# temp-stellwerk-a-3-laser-2.net
KiCad netlist of a schematic drawn in EAGLE
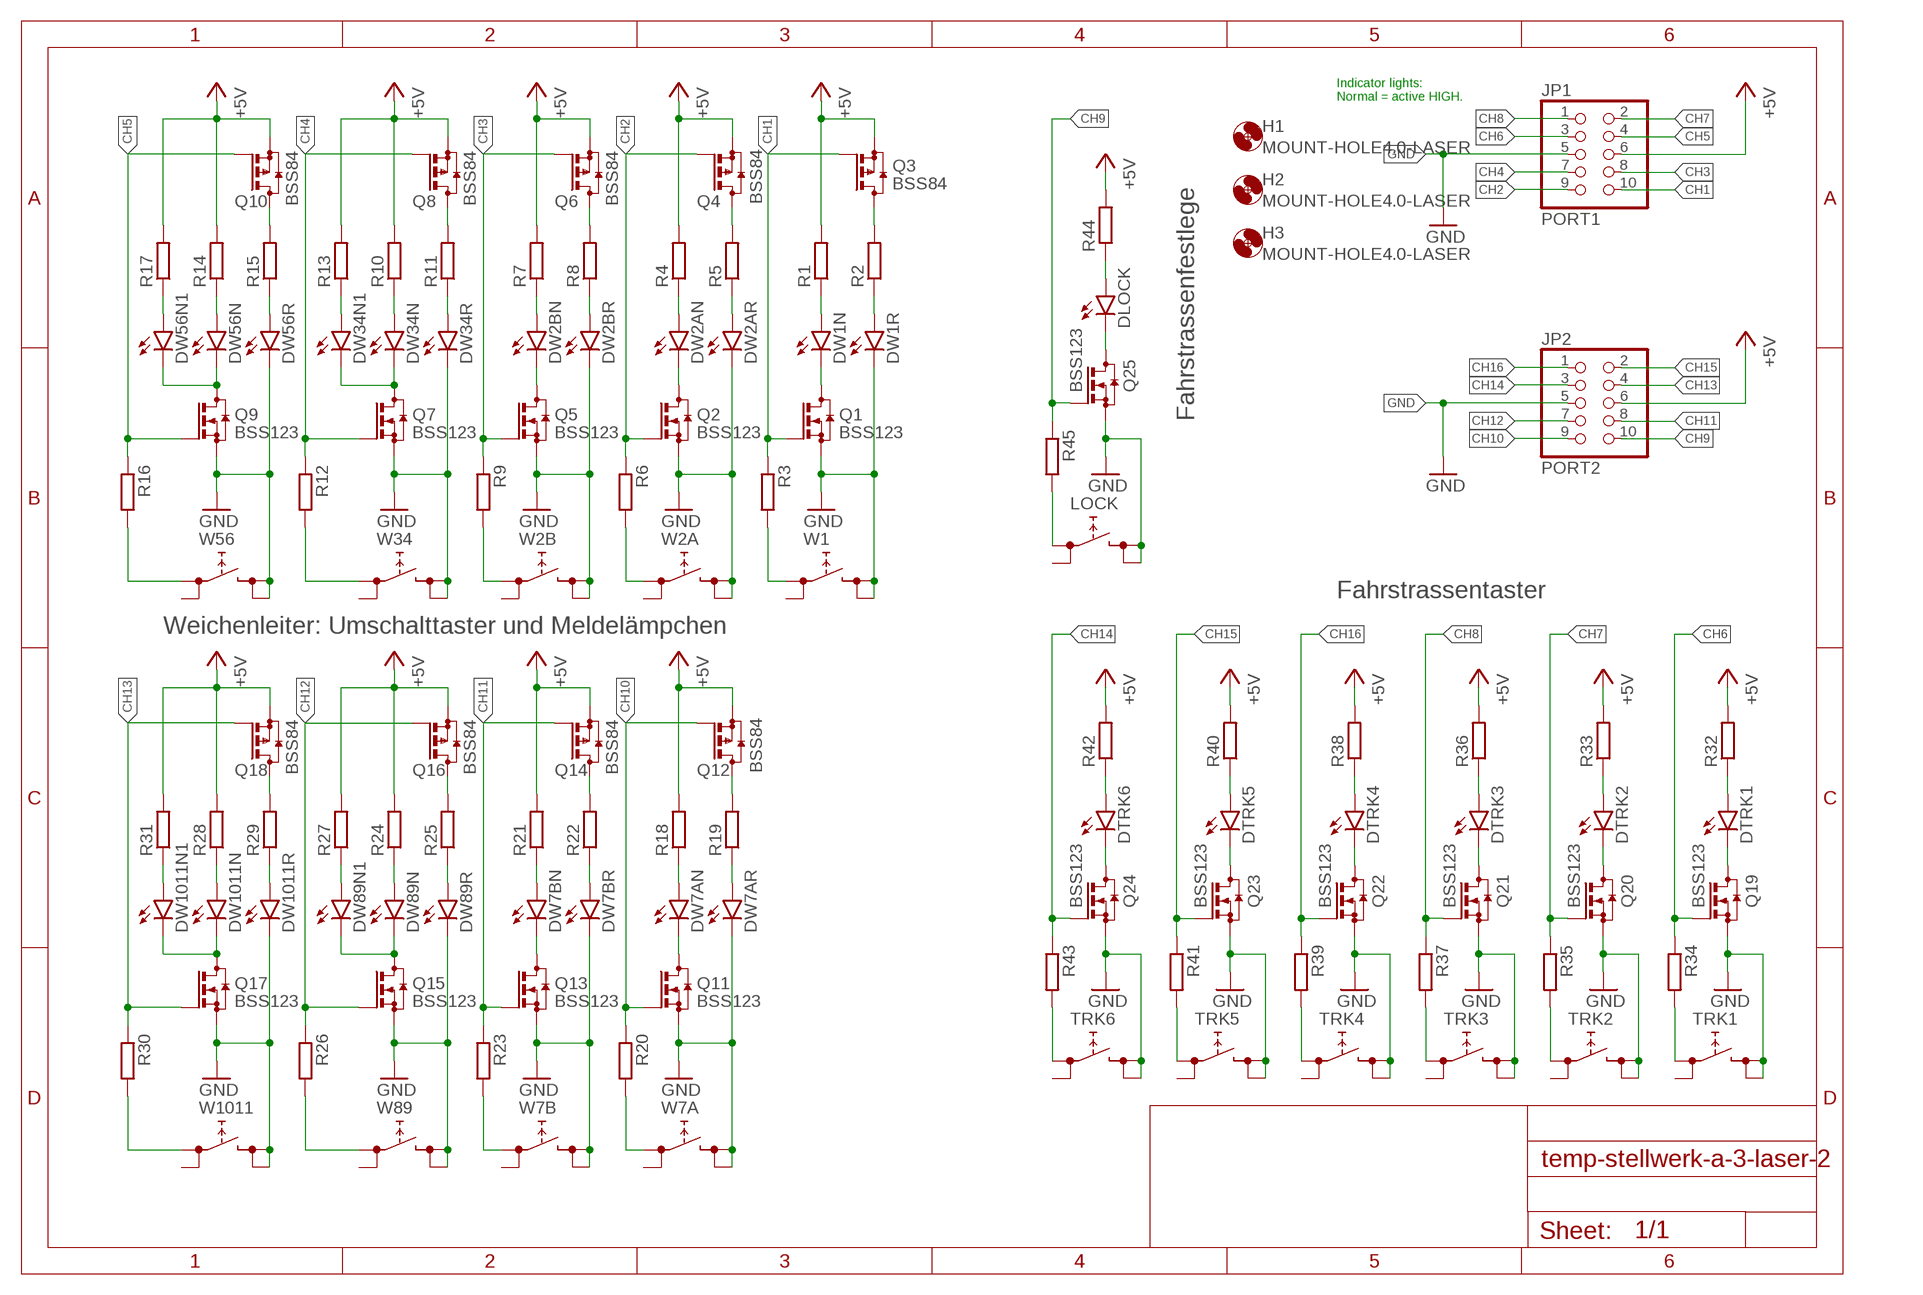
[diagram p0: schematic, sheet 1]

(export (version "E")
  (design (tool "Eeschema 10.0.6"))
  (components
    (comp (ref "DLOCK")
      (value "LEDCHIPLED_0805")
      (footprint "eagle-import:CHIPLED_0805")
      (libsource (lib "eagle-import") (part "LEDCHIPLED_0805"))
    )
    (comp (ref "DTRK1")
      (value "LEDCHIPLED_0805")
      (footprint "eagle-import:CHIPLED_0805")
      (libsource (lib "eagle-import") (part "LEDCHIPLED_0805"))
    )
    (comp (ref "DTRK2")
      (value "LEDCHIPLED_0805")
      (footprint "eagle-import:CHIPLED_0805")
      (libsource (lib "eagle-import") (part "LEDCHIPLED_0805"))
    )
    (comp (ref "DTRK3")
      (value "LEDCHIPLED_0805")
      (footprint "eagle-import:CHIPLED_0805")
      (libsource (lib "eagle-import") (part "LEDCHIPLED_0805"))
    )
    (comp (ref "DTRK4")
      (value "LEDCHIPLED_0805")
      (footprint "eagle-import:CHIPLED_0805")
      (libsource (lib "eagle-import") (part "LEDCHIPLED_0805"))
    )
    (comp (ref "DTRK5")
      (value "LEDCHIPLED_0805")
      (footprint "eagle-import:CHIPLED_0805")
      (libsource (lib "eagle-import") (part "LEDCHIPLED_0805"))
    )
    (comp (ref "DTRK6")
      (value "LEDCHIPLED_0805")
      (footprint "eagle-import:CHIPLED_0805")
      (libsource (lib "eagle-import") (part "LEDCHIPLED_0805"))
    )
    (comp (ref "DW1N")
      (value "LEDCHIPLED_0603")
      (footprint "eagle-import:CHIPLED_0603")
      (libsource (lib "eagle-import") (part "LEDCHIPLED_0603"))
    )
    (comp (ref "DW1R")
      (value "LEDCHIPLED_0603")
      (footprint "eagle-import:CHIPLED_0603")
      (libsource (lib "eagle-import") (part "LEDCHIPLED_0603"))
    )
    (comp (ref "DW2AN")
      (value "LEDCHIPLED_0603")
      (footprint "eagle-import:CHIPLED_0603")
      (libsource (lib "eagle-import") (part "LEDCHIPLED_0603"))
    )
    (comp (ref "DW2AR")
      (value "LEDCHIPLED_0603")
      (footprint "eagle-import:CHIPLED_0603")
      (libsource (lib "eagle-import") (part "LEDCHIPLED_0603"))
    )
    (comp (ref "DW2BN")
      (value "LEDCHIPLED_0805")
      (footprint "eagle-import:CHIPLED_0805")
      (libsource (lib "eagle-import") (part "LEDCHIPLED_0805"))
    )
    (comp (ref "DW2BR")
      (value "LEDCHIPLED_0805")
      (footprint "eagle-import:CHIPLED_0805")
      (libsource (lib "eagle-import") (part "LEDCHIPLED_0805"))
    )
    (comp (ref "DW7AN")
      (value "LEDCHIPLED_0603")
      (footprint "eagle-import:CHIPLED_0603")
      (libsource (lib "eagle-import") (part "led_259_LEDCHIPLED_0603"))
    )
    (comp (ref "DW7AR")
      (value "LEDCHIPLED_0603")
      (footprint "eagle-import:CHIPLED_0603")
      (libsource (lib "eagle-import") (part "LEDCHIPLED_0603"))
    )
    (comp (ref "DW7BN")
      (value "LEDCHIPLED_0805")
      (footprint "eagle-import:CHIPLED_0805")
      (libsource (lib "eagle-import") (part "LEDCHIPLED_0805"))
    )
    (comp (ref "DW7BR")
      (value "LEDCHIPLED_0805")
      (footprint "eagle-import:CHIPLED_0805")
      (libsource (lib "eagle-import") (part "LEDCHIPLED_0805"))
    )
    (comp (ref "DW34N")
      (value "LEDCHIPLED_0805")
      (footprint "eagle-import:CHIPLED_0805")
      (libsource (lib "eagle-import") (part "LEDCHIPLED_0805"))
    )
    (comp (ref "DW34N1")
      (value "LEDCHIPLED_0805")
      (footprint "eagle-import:CHIPLED_0805")
      (libsource (lib "eagle-import") (part "LEDCHIPLED_0805"))
    )
    (comp (ref "DW34R")
      (value "LEDCHIPLED_0805")
      (footprint "eagle-import:CHIPLED_0805")
      (libsource (lib "eagle-import") (part "LEDCHIPLED_0805"))
    )
    (comp (ref "DW56N")
      (value "LEDCHIPLED_0805")
      (footprint "eagle-import:CHIPLED_0805")
      (libsource (lib "eagle-import") (part "LEDCHIPLED_0805"))
    )
    (comp (ref "DW56N1")
      (value "LEDCHIPLED_0805")
      (footprint "eagle-import:CHIPLED_0805")
      (libsource (lib "eagle-import") (part "LEDCHIPLED_0805"))
    )
    (comp (ref "DW56R")
      (value "LEDCHIPLED_0805")
      (footprint "eagle-import:CHIPLED_0805")
      (libsource (lib "eagle-import") (part "LEDCHIPLED_0805"))
    )
    (comp (ref "DW89N")
      (value "LEDCHIPLED_0805")
      (footprint "eagle-import:CHIPLED_0805")
      (libsource (lib "eagle-import") (part "LEDCHIPLED_0805"))
    )
    (comp (ref "DW89N1")
      (value "LEDCHIPLED_0805")
      (footprint "eagle-import:CHIPLED_0805")
      (libsource (lib "eagle-import") (part "LEDCHIPLED_0805"))
    )
    (comp (ref "DW89R")
      (value "LEDCHIPLED_0805")
      (footprint "eagle-import:CHIPLED_0805")
      (libsource (lib "eagle-import") (part "LEDCHIPLED_0805"))
    )
    (comp (ref "DW1011N")
      (value "LEDCHIPLED_0805")
      (footprint "eagle-import:CHIPLED_0805")
      (libsource (lib "eagle-import") (part "LEDCHIPLED_0805"))
    )
    (comp (ref "DW1011N1")
      (value "LEDCHIPLED_0805")
      (footprint "eagle-import:CHIPLED_0805")
      (libsource (lib "eagle-import") (part "LEDCHIPLED_0805"))
    )
    (comp (ref "DW1011R")
      (value "LEDCHIPLED_0805")
      (footprint "eagle-import:CHIPLED_0805")
      (libsource (lib "eagle-import") (part "LEDCHIPLED_0805"))
    )
    (comp (ref "H1")
      (value "MOUNT-HOLE4.0-LASER")
      (footprint "eagle-import:MOUNT-HOLE-3.2-4.0-LASER")
      (libsource (lib "eagle-import") (part "MOUNT-HOLE4.0-LASER"))
    )
    (comp (ref "H2")
      (value "MOUNT-HOLE4.0-LASER")
      (footprint "eagle-import:MOUNT-HOLE-3.2-4.0-LASER")
      (libsource (lib "eagle-import") (part "MOUNT-HOLE4.0-LASER"))
    )
    (comp (ref "H3")
      (value "MOUNT-HOLE4.0-LASER")
      (footprint "eagle-import:MOUNT-HOLE-3.2-4.0-LASER")
      (libsource (lib "eagle-import") (part "MOUNT-HOLE4.0-LASER"))
    )
    (comp (ref "JP1")
      (value "PORT1")
      (footprint "eagle-import:CON10M")
      (libsource (lib "eagle-import") (part "PINHD-2X5CN"))
    )
    (comp (ref "JP2")
      (value "PORT2")
      (footprint "eagle-import:CON10M")
      (libsource (lib "eagle-import") (part "PINHD-2X5CN"))
    )
    (comp (ref "LOCK")
      (value "LOCK")
      (footprint "eagle-import:TACTSW-6X6-LASER")
      (libsource (lib "eagle-import") (part "TACTSW-6X6S"))
    )
    (comp (ref "Q1")
      (value "BSS123")
      (footprint "eagle-import:SOT23-NCH")
      (libsource (lib "eagle-import") (part "BSS123"))
    )
    (comp (ref "Q2")
      (value "BSS123")
      (footprint "eagle-import:SOT23-NCH")
      (libsource (lib "eagle-import") (part "BSS123"))
    )
    (comp (ref "Q3")
      (value "BSS84")
      (footprint "eagle-import:SOT23")
      (libsource (lib "eagle-import") (part "BSS84"))
    )
    (comp (ref "Q4")
      (value "BSS84")
      (footprint "eagle-import:SOT23")
      (libsource (lib "eagle-import") (part "BSS84"))
    )
    (comp (ref "Q5")
      (value "BSS123")
      (footprint "eagle-import:SOT23-NCH")
      (libsource (lib "eagle-import") (part "BSS123"))
    )
    (comp (ref "Q6")
      (value "BSS84")
      (footprint "eagle-import:SOT23")
      (libsource (lib "eagle-import") (part "BSS84"))
    )
    (comp (ref "Q7")
      (value "BSS123")
      (footprint "eagle-import:SOT23-NCH")
      (libsource (lib "eagle-import") (part "BSS123"))
    )
    (comp (ref "Q8")
      (value "BSS84")
      (footprint "eagle-import:SOT23")
      (libsource (lib "eagle-import") (part "BSS84"))
    )
    (comp (ref "Q9")
      (value "BSS123")
      (footprint "eagle-import:SOT23-NCH")
      (libsource (lib "eagle-import") (part "BSS123"))
    )
    (comp (ref "Q10")
      (value "BSS84")
      (footprint "eagle-import:SOT23")
      (libsource (lib "eagle-import") (part "BSS84"))
    )
    (comp (ref "Q11")
      (value "BSS123")
      (footprint "eagle-import:SOT23-NCH")
      (libsource (lib "eagle-import") (part "BSS123"))
    )
    (comp (ref "Q12")
      (value "BSS84")
      (footprint "eagle-import:SOT23")
      (libsource (lib "eagle-import") (part "BSS84"))
    )
    (comp (ref "Q13")
      (value "BSS123")
      (footprint "eagle-import:SOT23-NCH")
      (libsource (lib "eagle-import") (part "BSS123"))
    )
    (comp (ref "Q14")
      (value "BSS84")
      (footprint "eagle-import:SOT23")
      (libsource (lib "eagle-import") (part "BSS84"))
    )
    (comp (ref "Q15")
      (value "BSS123")
      (footprint "eagle-import:SOT23-NCH")
      (libsource (lib "eagle-import") (part "BSS123"))
    )
    (comp (ref "Q16")
      (value "BSS84")
      (footprint "eagle-import:SOT23")
      (libsource (lib "eagle-import") (part "BSS84"))
    )
    (comp (ref "Q17")
      (value "BSS123")
      (footprint "eagle-import:SOT23-NCH")
      (libsource (lib "eagle-import") (part "BSS123"))
    )
    (comp (ref "Q18")
      (value "BSS84")
      (footprint "eagle-import:SOT23")
      (libsource (lib "eagle-import") (part "BSS84"))
    )
    (comp (ref "Q19")
      (value "BSS123")
      (footprint "eagle-import:SOT23-NCH")
      (libsource (lib "eagle-import") (part "BSS123"))
    )
    (comp (ref "Q20")
      (value "BSS123")
      (footprint "eagle-import:SOT23-NCH")
      (libsource (lib "eagle-import") (part "BSS123"))
    )
    (comp (ref "Q21")
      (value "BSS123")
      (footprint "eagle-import:SOT23-NCH")
      (libsource (lib "eagle-import") (part "BSS123"))
    )
    (comp (ref "Q22")
      (value "BSS123")
      (footprint "eagle-import:SOT23-NCH")
      (libsource (lib "eagle-import") (part "BSS123"))
    )
    (comp (ref "Q23")
      (value "BSS123")
      (footprint "eagle-import:SOT23-NCH")
      (libsource (lib "eagle-import") (part "BSS123"))
    )
    (comp (ref "Q24")
      (value "BSS123")
      (footprint "eagle-import:SOT23-NCH")
      (libsource (lib "eagle-import") (part "BSS123"))
    )
    (comp (ref "Q25")
      (value "BSS123")
      (footprint "eagle-import:SOT23-NCH")
      (libsource (lib "eagle-import") (part "BSS123"))
    )
    (comp (ref "R1")
      (value "R-EU_R0805")
      (footprint "eagle-import:R0805")
      (libsource (lib "eagle-import") (part "R-EU_R0805"))
    )
    (comp (ref "R2")
      (value "R-EU_R0805")
      (footprint "eagle-import:R0805")
      (libsource (lib "eagle-import") (part "R-EU_R0805"))
    )
    (comp (ref "R3")
      (value "R-EU_R0805")
      (footprint "eagle-import:R0805")
      (libsource (lib "eagle-import") (part "R-EU_R0805"))
    )
    (comp (ref "R4")
      (value "R-EU_R0805")
      (footprint "eagle-import:R0805")
      (libsource (lib "eagle-import") (part "R-EU_R0805"))
    )
    (comp (ref "R5")
      (value "R-EU_R0805")
      (footprint "eagle-import:R0805")
      (libsource (lib "eagle-import") (part "R-EU_R0805"))
    )
    (comp (ref "R6")
      (value "R-EU_R0805")
      (footprint "eagle-import:R0805")
      (libsource (lib "eagle-import") (part "R-EU_R0805"))
    )
    (comp (ref "R7")
      (value "R-EU_R0805")
      (footprint "eagle-import:R0805")
      (libsource (lib "eagle-import") (part "R-EU_R0805"))
    )
    (comp (ref "R8")
      (value "R-EU_R0805")
      (footprint "eagle-import:R0805")
      (libsource (lib "eagle-import") (part "R-EU_R0805"))
    )
    (comp (ref "R9")
      (value "R-EU_R0805")
      (footprint "eagle-import:R0805")
      (libsource (lib "eagle-import") (part "R-EU_R0805"))
    )
    (comp (ref "R10")
      (value "R-EU_R0805")
      (footprint "eagle-import:R0805")
      (libsource (lib "eagle-import") (part "R-EU_R0805"))
    )
    (comp (ref "R11")
      (value "R-EU_R0805")
      (footprint "eagle-import:R0805")
      (libsource (lib "eagle-import") (part "R-EU_R0805"))
    )
    (comp (ref "R12")
      (value "R-EU_R0805")
      (footprint "eagle-import:R0805")
      (libsource (lib "eagle-import") (part "R-EU_R0805"))
    )
    (comp (ref "R13")
      (value "R-EU_R0805")
      (footprint "eagle-import:R0805")
      (libsource (lib "eagle-import") (part "R-EU_R0805"))
    )
    (comp (ref "R14")
      (value "R-EU_R0805")
      (footprint "eagle-import:R0805")
      (libsource (lib "eagle-import") (part "R-EU_R0805"))
    )
    (comp (ref "R15")
      (value "R-EU_R0805")
      (footprint "eagle-import:R0805")
      (libsource (lib "eagle-import") (part "R-EU_R0805"))
    )
    (comp (ref "R16")
      (value "R-EU_R0805")
      (footprint "eagle-import:R0805")
      (libsource (lib "eagle-import") (part "R-EU_R0805"))
    )
    (comp (ref "R17")
      (value "R-EU_R0805")
      (footprint "eagle-import:R0805")
      (libsource (lib "eagle-import") (part "R-EU_R0805"))
    )
    (comp (ref "R18")
      (value "R-EU_R0805")
      (footprint "eagle-import:R0805")
      (libsource (lib "eagle-import") (part "R-EU_R0805"))
    )
    (comp (ref "R19")
      (value "R-EU_R0805")
      (footprint "eagle-import:R0805")
      (libsource (lib "eagle-import") (part "R-EU_R0805"))
    )
    (comp (ref "R20")
      (value "R-EU_R0805")
      (footprint "eagle-import:R0805")
      (libsource (lib "eagle-import") (part "R-EU_R0805"))
    )
    (comp (ref "R21")
      (value "R-EU_R0805")
      (footprint "eagle-import:R0805")
      (libsource (lib "eagle-import") (part "R-EU_R0805"))
    )
    (comp (ref "R22")
      (value "R-EU_R0805")
      (footprint "eagle-import:R0805")
      (libsource (lib "eagle-import") (part "R-EU_R0805"))
    )
    (comp (ref "R23")
      (value "R-EU_R0805")
      (footprint "eagle-import:R0805")
      (libsource (lib "eagle-import") (part "R-EU_R0805"))
    )
    (comp (ref "R24")
      (value "R-EU_R0805")
      (footprint "eagle-import:R0805")
      (libsource (lib "eagle-import") (part "R-EU_R0805"))
    )
    (comp (ref "R25")
      (value "R-EU_R0805")
      (footprint "eagle-import:R0805")
      (libsource (lib "eagle-import") (part "R-EU_R0805"))
    )
    (comp (ref "R26")
      (value "R-EU_R0805")
      (footprint "eagle-import:R0805")
      (libsource (lib "eagle-import") (part "R-EU_R0805"))
    )
    (comp (ref "R27")
      (value "R-EU_R0805")
      (footprint "eagle-import:R0805")
      (libsource (lib "eagle-import") (part "R-EU_R0805"))
    )
    (comp (ref "R28")
      (value "R-EU_R0805")
      (footprint "eagle-import:R0805")
      (libsource (lib "eagle-import") (part "R-EU_R0805"))
    )
    (comp (ref "R29")
      (value "R-EU_R0805")
      (footprint "eagle-import:R0805")
      (libsource (lib "eagle-import") (part "R-EU_R0805"))
    )
    (comp (ref "R30")
      (value "R-EU_R0805")
      (footprint "eagle-import:R0805")
      (libsource (lib "eagle-import") (part "R-EU_R0805"))
    )
    (comp (ref "R31")
      (value "R-EU_R0805")
      (footprint "eagle-import:R0805")
      (libsource (lib "eagle-import") (part "R-EU_R0805"))
    )
    (comp (ref "R32")
      (value "R-EU_R0805")
      (footprint "eagle-import:R0805")
      (libsource (lib "eagle-import") (part "R-EU_R0805"))
    )
    (comp (ref "R33")
      (value "R-EU_R0805")
      (footprint "eagle-import:R0805")
      (libsource (lib "eagle-import") (part "R-EU_R0805"))
    )
    (comp (ref "R34")
      (value "R-EU_R0805")
      (footprint "eagle-import:R0805")
      (libsource (lib "eagle-import") (part "R-EU_R0805"))
    )
    (comp (ref "R35")
      (value "R-EU_R0805")
      (footprint "eagle-import:R0805")
      (libsource (lib "eagle-import") (part "R-EU_R0805"))
    )
    (comp (ref "R36")
      (value "R-EU_R0805")
      (footprint "eagle-import:R0805")
      (libsource (lib "eagle-import") (part "R-EU_R0805"))
    )
    (comp (ref "R37")
      (value "R-EU_R0805")
      (footprint "eagle-import:R0805")
      (libsource (lib "eagle-import") (part "R-EU_R0805"))
    )
    (comp (ref "R38")
      (value "R-EU_R0805")
      (footprint "eagle-import:R0805")
      (libsource (lib "eagle-import") (part "R-EU_R0805"))
    )
    (comp (ref "R39")
      (value "R-EU_R0805")
      (footprint "eagle-import:R0805")
      (libsource (lib "eagle-import") (part "R-EU_R0805"))
    )
    (comp (ref "R40")
      (value "R-EU_R0805")
      (footprint "eagle-import:R0805")
      (libsource (lib "eagle-import") (part "R-EU_R0805"))
    )
    (comp (ref "R41")
      (value "R-EU_R0805")
      (footprint "eagle-import:R0805")
      (libsource (lib "eagle-import") (part "R-EU_R0805"))
    )
    (comp (ref "R42")
      (value "R-EU_R0805")
      (footprint "eagle-import:R0805")
      (libsource (lib "eagle-import") (part "R-EU_R0805"))
    )
    (comp (ref "R43")
      (value "R-EU_R0805")
      (footprint "eagle-import:R0805")
      (libsource (lib "eagle-import") (part "R-EU_R0805"))
    )
    (comp (ref "R44")
      (value "R-EU_R0805")
      (footprint "eagle-import:R0805")
      (libsource (lib "eagle-import") (part "R-EU_R0805"))
    )
    (comp (ref "R45")
      (value "R-EU_R0805")
      (footprint "eagle-import:R0805")
      (libsource (lib "eagle-import") (part "R-EU_R0805"))
    )
    (comp (ref "TRK1")
      (value "TACTSW-6X6S")
      (footprint "eagle-import:TACTSW-6X6-LASER")
      (libsource (lib "eagle-import") (part "TACTSW-6X6S"))
    )
    (comp (ref "TRK2")
      (value "TACTSW-6X6S")
      (footprint "eagle-import:TACTSW-6X6-LASER")
      (libsource (lib "eagle-import") (part "TACTSW-6X6S"))
    )
    (comp (ref "TRK3")
      (value "TACTSW-6X6S")
      (footprint "eagle-import:TACTSW-6X6-LASER")
      (libsource (lib "eagle-import") (part "TACTSW-6X6S"))
    )
    (comp (ref "TRK4")
      (value "TACTSW-6X6S")
      (footprint "eagle-import:TACTSW-6X6-LASER")
      (libsource (lib "eagle-import") (part "TACTSW-6X6S"))
    )
    (comp (ref "TRK5")
      (value "TACTSW-6X6S")
      (footprint "eagle-import:TACTSW-6X6-LASER")
      (libsource (lib "eagle-import") (part "TACTSW-6X6S"))
    )
    (comp (ref "TRK6")
      (value "TACTSW-6X6S")
      (footprint "eagle-import:TACTSW-6X6-LASER")
      (libsource (lib "eagle-import") (part "TACTSW-6X6S"))
    )
    (comp (ref "W1")
      (value "W1")
      (footprint "eagle-import:TACTSW-6X6-LASER")
      (libsource (lib "eagle-import") (part "TACTSW-6X6S"))
    )
    (comp (ref "W2A")
      (value "TACTSW-6X6S")
      (footprint "eagle-import:TACTSW-6X6-LASER")
      (libsource (lib "eagle-import") (part "TACTSW-6X6S"))
    )
    (comp (ref "W2B")
      (value "TACTSW-6X6S")
      (footprint "eagle-import:TACTSW-6X6-LASER")
      (libsource (lib "eagle-import") (part "TACTSW-6X6S"))
    )
    (comp (ref "W7A")
      (value "TACTSW-6X6S")
      (footprint "eagle-import:TACTSW-6X6-LASER")
      (libsource (lib "eagle-import") (part "TACTSW-6X6S"))
    )
    (comp (ref "W7B")
      (value "TACTSW-6X6S")
      (footprint "eagle-import:TACTSW-6X6-LASER")
      (libsource (lib "eagle-import") (part "TACTSW-6X6S"))
    )
    (comp (ref "W34")
      (value "XOVER")
      (footprint "eagle-import:TACTSW-6X6-LASER")
      (libsource (lib "eagle-import") (part "TACTSW-6X6S"))
    )
    (comp (ref "W56")
      (value "XOVER")
      (footprint "eagle-import:TACTSW-6X6-LASER")
      (libsource (lib "eagle-import") (part "TACTSW-6X6S"))
    )
    (comp (ref "W89")
      (value "XOVER")
      (footprint "eagle-import:TACTSW-6X6-LASER")
      (libsource (lib "eagle-import") (part "TACTSW-6X6S"))
    )
    (comp (ref "W1011")
      (value "XOVER")
      (footprint "eagle-import:TACTSW-6X6-LASER")
      (libsource (lib "eagle-import") (part "TACTSW-6X6S"))
    )
  )
  (nets
    (net (code "1") (name "+5V") (class "Default")
      (node (ref "JP1") (pin "6") (pinfunction "6_6") (pintype "passive"))
      (node (ref "JP2") (pin "6") (pinfunction "6_6") (pintype "passive"))
      (node (ref "Q10") (pin "2") (pinfunction "S_2") (pintype "passive"))
      (node (ref "Q12") (pin "2") (pinfunction "S_2") (pintype "passive"))
      (node (ref "Q14") (pin "2") (pinfunction "S_2") (pintype "passive"))
      (node (ref "Q16") (pin "2") (pinfunction "S_2") (pintype "passive"))
      (node (ref "Q18") (pin "2") (pinfunction "S_2") (pintype "passive"))
      (node (ref "Q3") (pin "2") (pinfunction "S_2") (pintype "passive"))
      (node (ref "Q4") (pin "2") (pinfunction "S_2") (pintype "passive"))
      (node (ref "Q6") (pin "2") (pinfunction "S_2") (pintype "passive"))
      (node (ref "Q8") (pin "2") (pinfunction "S_2") (pintype "passive"))
      (node (ref "R1") (pin "2") (pinfunction "2_2") (pintype "passive"))
      (node (ref "R10") (pin "2") (pinfunction "2_2") (pintype "passive"))
      (node (ref "R13") (pin "2") (pinfunction "2_2") (pintype "passive"))
      (node (ref "R14") (pin "2") (pinfunction "2_2") (pintype "passive"))
      (node (ref "R17") (pin "2") (pinfunction "2_2") (pintype "passive"))
      (node (ref "R18") (pin "2") (pinfunction "2_2") (pintype "passive"))
      (node (ref "R21") (pin "2") (pinfunction "2_2") (pintype "passive"))
      (node (ref "R24") (pin "2") (pinfunction "2_2") (pintype "passive"))
      (node (ref "R27") (pin "2") (pinfunction "2_2") (pintype "passive"))
      (node (ref "R28") (pin "2") (pinfunction "2_2") (pintype "passive"))
      (node (ref "R31") (pin "2") (pinfunction "2_2") (pintype "passive"))
      (node (ref "R32") (pin "2") (pinfunction "2_2") (pintype "passive"))
      (node (ref "R33") (pin "2") (pinfunction "2_2") (pintype "passive"))
      (node (ref "R36") (pin "2") (pinfunction "2_2") (pintype "passive"))
      (node (ref "R38") (pin "2") (pinfunction "2_2") (pintype "passive"))
      (node (ref "R4") (pin "2") (pinfunction "2_2") (pintype "passive"))
      (node (ref "R40") (pin "2") (pinfunction "2_2") (pintype "passive"))
      (node (ref "R42") (pin "2") (pinfunction "2_2") (pintype "passive"))
      (node (ref "R44") (pin "2") (pinfunction "2_2") (pintype "passive"))
      (node (ref "R7") (pin "2") (pinfunction "2_2") (pintype "passive"))
    )
    (net (code "2") (name "CH1") (class "Default")
      (node (ref "JP1") (pin "10") (pinfunction "10_10") (pintype "passive"))
      (node (ref "Q1") (pin "1") (pinfunction "G_1") (pintype "passive"))
      (node (ref "Q3") (pin "1") (pinfunction "G_1") (pintype "passive"))
      (node (ref "R3") (pin "1") (pinfunction "1_1") (pintype "passive"))
    )
    (net (code "3") (name "CH2") (class "Default")
      (node (ref "JP1") (pin "9") (pinfunction "9_9") (pintype "passive"))
      (node (ref "Q2") (pin "1") (pinfunction "G_1") (pintype "passive"))
      (node (ref "Q4") (pin "1") (pinfunction "G_1") (pintype "passive"))
      (node (ref "R6") (pin "1") (pinfunction "1_1") (pintype "passive"))
    )
    (net (code "4") (name "CH3") (class "Default")
      (node (ref "JP1") (pin "8") (pinfunction "8_8") (pintype "passive"))
      (node (ref "Q5") (pin "1") (pinfunction "G_1") (pintype "passive"))
      (node (ref "Q6") (pin "1") (pinfunction "G_1") (pintype "passive"))
      (node (ref "R9") (pin "1") (pinfunction "1_1") (pintype "passive"))
    )
    (net (code "5") (name "CH4") (class "Default")
      (node (ref "JP1") (pin "7") (pinfunction "7_7") (pintype "passive"))
      (node (ref "Q7") (pin "1") (pinfunction "G_1") (pintype "passive"))
      (node (ref "Q8") (pin "1") (pinfunction "G_1") (pintype "passive"))
      (node (ref "R12") (pin "1") (pinfunction "1_1") (pintype "passive"))
    )
    (net (code "6") (name "CH5") (class "Default")
      (node (ref "JP1") (pin "4") (pinfunction "4_4") (pintype "passive"))
      (node (ref "Q10") (pin "1") (pinfunction "G_1") (pintype "passive"))
      (node (ref "Q9") (pin "1") (pinfunction "G_1") (pintype "passive"))
      (node (ref "R16") (pin "1") (pinfunction "1_1") (pintype "passive"))
    )
    (net (code "7") (name "CH6") (class "Default")
      (node (ref "JP1") (pin "3") (pinfunction "3_3") (pintype "passive"))
      (node (ref "Q19") (pin "1") (pinfunction "G_1") (pintype "passive"))
      (node (ref "R34") (pin "1") (pinfunction "1_1") (pintype "passive"))
    )
    (net (code "8") (name "CH7") (class "Default")
      (node (ref "JP1") (pin "2") (pinfunction "2_2") (pintype "passive"))
      (node (ref "Q20") (pin "1") (pinfunction "G_1") (pintype "passive"))
      (node (ref "R35") (pin "1") (pinfunction "1_1") (pintype "passive"))
    )
    (net (code "9") (name "CH8") (class "Default")
      (node (ref "JP1") (pin "1") (pinfunction "1_1") (pintype "passive"))
      (node (ref "Q21") (pin "1") (pinfunction "G_1") (pintype "passive"))
      (node (ref "R37") (pin "1") (pinfunction "1_1") (pintype "passive"))
    )
    (net (code "10") (name "CH9") (class "Default")
      (node (ref "JP2") (pin "10") (pinfunction "10_10") (pintype "passive"))
      (node (ref "Q25") (pin "1") (pinfunction "G_1") (pintype "passive"))
      (node (ref "R45") (pin "1") (pinfunction "1_1") (pintype "passive"))
    )
    (net (code "11") (name "CH10") (class "Default")
      (node (ref "JP2") (pin "9") (pinfunction "9_9") (pintype "passive"))
      (node (ref "Q11") (pin "1") (pinfunction "G_1") (pintype "passive"))
      (node (ref "Q12") (pin "1") (pinfunction "G_1") (pintype "passive"))
      (node (ref "R20") (pin "1") (pinfunction "1_1") (pintype "passive"))
    )
    (net (code "12") (name "CH11") (class "Default")
      (node (ref "JP2") (pin "8") (pinfunction "8_8") (pintype "passive"))
      (node (ref "Q13") (pin "1") (pinfunction "G_1") (pintype "passive"))
      (node (ref "Q14") (pin "1") (pinfunction "G_1") (pintype "passive"))
      (node (ref "R23") (pin "1") (pinfunction "1_1") (pintype "passive"))
    )
    (net (code "13") (name "CH12") (class "Default")
      (node (ref "JP2") (pin "7") (pinfunction "7_7") (pintype "passive"))
      (node (ref "Q15") (pin "1") (pinfunction "G_1") (pintype "passive"))
      (node (ref "Q16") (pin "1") (pinfunction "G_1") (pintype "passive"))
      (node (ref "R26") (pin "1") (pinfunction "1_1") (pintype "passive"))
    )
    (net (code "14") (name "CH13") (class "Default")
      (node (ref "JP2") (pin "4") (pinfunction "4_4") (pintype "passive"))
      (node (ref "Q17") (pin "1") (pinfunction "G_1") (pintype "passive"))
      (node (ref "Q18") (pin "1") (pinfunction "G_1") (pintype "passive"))
      (node (ref "R30") (pin "1") (pinfunction "1_1") (pintype "passive"))
    )
    (net (code "15") (name "CH14") (class "Default")
      (node (ref "JP2") (pin "3") (pinfunction "3_3") (pintype "passive"))
      (node (ref "Q24") (pin "1") (pinfunction "G_1") (pintype "passive"))
      (node (ref "R43") (pin "1") (pinfunction "1_1") (pintype "passive"))
    )
    (net (code "16") (name "CH15") (class "Default")
      (node (ref "JP2") (pin "2") (pinfunction "2_2") (pintype "passive"))
      (node (ref "Q23") (pin "1") (pinfunction "G_1") (pintype "passive"))
      (node (ref "R41") (pin "1") (pinfunction "1_1") (pintype "passive"))
    )
    (net (code "17") (name "CH16") (class "Default")
      (node (ref "JP2") (pin "1") (pinfunction "1_1") (pintype "passive"))
      (node (ref "Q22") (pin "1") (pinfunction "G_1") (pintype "passive"))
      (node (ref "R39") (pin "1") (pinfunction "1_1") (pintype "passive"))
    )
    (net (code "18") (name "GND") (class "Default")
      (node (ref "DW1011R") (pin "C") (pinfunction "C_C") (pintype "passive"))
      (node (ref "DW1R") (pin "C") (pinfunction "C_C") (pintype "passive"))
      (node (ref "DW2AR") (pin "C") (pinfunction "C_C") (pintype "passive"))
      (node (ref "DW2BR") (pin "C") (pinfunction "C_C") (pintype "passive"))
      (node (ref "DW34R") (pin "C") (pinfunction "C_C") (pintype "passive"))
      (node (ref "DW56R") (pin "C") (pinfunction "C_C") (pintype "passive"))
      (node (ref "DW7AR") (pin "C") (pinfunction "C_C") (pintype "passive"))
      (node (ref "DW7BR") (pin "C") (pinfunction "C_C") (pintype "passive"))
      (node (ref "DW89R") (pin "C") (pinfunction "C_C") (pintype "passive"))
      (node (ref "JP1") (pin "5") (pinfunction "5_5") (pintype "passive"))
      (node (ref "JP2") (pin "5") (pinfunction "5_5") (pintype "passive"))
      (node (ref "LOCK") (pin "3") (pinfunction "2.1_3") (pintype "passive"))
      (node (ref "LOCK") (pin "4") (pinfunction "2.2_4") (pintype "passive"))
      (node (ref "Q1") (pin "2") (pinfunction "S_2") (pintype "passive"))
      (node (ref "Q11") (pin "2") (pinfunction "S_2") (pintype "passive"))
      (node (ref "Q13") (pin "2") (pinfunction "S_2") (pintype "passive"))
      (node (ref "Q15") (pin "2") (pinfunction "S_2") (pintype "passive"))
      (node (ref "Q17") (pin "2") (pinfunction "S_2") (pintype "passive"))
      (node (ref "Q19") (pin "2") (pinfunction "S_2") (pintype "passive"))
      (node (ref "Q2") (pin "2") (pinfunction "S_2") (pintype "passive"))
      (node (ref "Q20") (pin "2") (pinfunction "S_2") (pintype "passive"))
      (node (ref "Q21") (pin "2") (pinfunction "S_2") (pintype "passive"))
      (node (ref "Q22") (pin "2") (pinfunction "S_2") (pintype "passive"))
      (node (ref "Q23") (pin "2") (pinfunction "S_2") (pintype "passive"))
      (node (ref "Q24") (pin "2") (pinfunction "S_2") (pintype "passive"))
      (node (ref "Q25") (pin "2") (pinfunction "S_2") (pintype "passive"))
      (node (ref "Q5") (pin "2") (pinfunction "S_2") (pintype "passive"))
      (node (ref "Q7") (pin "2") (pinfunction "S_2") (pintype "passive"))
      (node (ref "Q9") (pin "2") (pinfunction "S_2") (pintype "passive"))
      (node (ref "TRK1") (pin "3") (pinfunction "2.1_3") (pintype "passive"))
      (node (ref "TRK1") (pin "4") (pinfunction "2.2_4") (pintype "passive"))
      (node (ref "TRK2") (pin "3") (pinfunction "2.1_3") (pintype "passive"))
      (node (ref "TRK2") (pin "4") (pinfunction "2.2_4") (pintype "passive"))
      (node (ref "TRK3") (pin "3") (pinfunction "2.1_3") (pintype "passive"))
      (node (ref "TRK3") (pin "4") (pinfunction "2.2_4") (pintype "passive"))
      (node (ref "TRK4") (pin "3") (pinfunction "2.1_3") (pintype "passive"))
      (node (ref "TRK4") (pin "4") (pinfunction "2.2_4") (pintype "passive"))
      (node (ref "TRK5") (pin "3") (pinfunction "2.1_3") (pintype "passive"))
      (node (ref "TRK5") (pin "4") (pinfunction "2.2_4") (pintype "passive"))
      (node (ref "TRK6") (pin "3") (pinfunction "2.1_3") (pintype "passive"))
      (node (ref "TRK6") (pin "4") (pinfunction "2.2_4") (pintype "passive"))
      (node (ref "W1") (pin "3") (pinfunction "2.1_3") (pintype "passive"))
      (node (ref "W1") (pin "4") (pinfunction "2.2_4") (pintype "passive"))
      (node (ref "W1011") (pin "3") (pinfunction "2.1_3") (pintype "passive"))
      (node (ref "W1011") (pin "4") (pinfunction "2.2_4") (pintype "passive"))
      (node (ref "W2A") (pin "3") (pinfunction "2.1_3") (pintype "passive"))
      (node (ref "W2A") (pin "4") (pinfunction "2.2_4") (pintype "passive"))
      (node (ref "W2B") (pin "3") (pinfunction "2.1_3") (pintype "passive"))
      (node (ref "W2B") (pin "4") (pinfunction "2.2_4") (pintype "passive"))
      (node (ref "W34") (pin "3") (pinfunction "2.1_3") (pintype "passive"))
      (node (ref "W34") (pin "4") (pinfunction "2.2_4") (pintype "passive"))
      (node (ref "W56") (pin "3") (pinfunction "2.1_3") (pintype "passive"))
      (node (ref "W56") (pin "4") (pinfunction "2.2_4") (pintype "passive"))
      (node (ref "W7A") (pin "3") (pinfunction "2.1_3") (pintype "passive"))
      (node (ref "W7A") (pin "4") (pinfunction "2.2_4") (pintype "passive"))
      (node (ref "W7B") (pin "3") (pinfunction "2.1_3") (pintype "passive"))
      (node (ref "W7B") (pin "4") (pinfunction "2.2_4") (pintype "passive"))
      (node (ref "W89") (pin "3") (pinfunction "2.1_3") (pintype "passive"))
      (node (ref "W89") (pin "4") (pinfunction "2.2_4") (pintype "passive"))
    )
    (net (code "19") (name "Net-(DLOCK-PadA)") (class "Default")
      (node (ref "DLOCK") (pin "A") (pinfunction "A_A") (pintype "passive"))
      (node (ref "R44") (pin "1") (pinfunction "1_1") (pintype "passive"))
    )
    (net (code "20") (name "Net-(DTRK1-PadA)") (class "Default")
      (node (ref "DTRK1") (pin "A") (pinfunction "A_A") (pintype "passive"))
      (node (ref "R32") (pin "1") (pinfunction "1_1") (pintype "passive"))
    )
    (net (code "21") (name "Net-(DTRK2-PadA)") (class "Default")
      (node (ref "DTRK2") (pin "A") (pinfunction "A_A") (pintype "passive"))
      (node (ref "R33") (pin "1") (pinfunction "1_1") (pintype "passive"))
    )
    (net (code "22") (name "Net-(DTRK3-PadA)") (class "Default")
      (node (ref "DTRK3") (pin "A") (pinfunction "A_A") (pintype "passive"))
      (node (ref "R36") (pin "1") (pinfunction "1_1") (pintype "passive"))
    )
    (net (code "23") (name "Net-(DTRK4-PadA)") (class "Default")
      (node (ref "DTRK4") (pin "A") (pinfunction "A_A") (pintype "passive"))
      (node (ref "R38") (pin "1") (pinfunction "1_1") (pintype "passive"))
    )
    (net (code "24") (name "Net-(DTRK5-PadA)") (class "Default")
      (node (ref "DTRK5") (pin "A") (pinfunction "A_A") (pintype "passive"))
      (node (ref "R40") (pin "1") (pinfunction "1_1") (pintype "passive"))
    )
    (net (code "25") (name "Net-(DTRK6-PadA)") (class "Default")
      (node (ref "DTRK6") (pin "A") (pinfunction "A_A") (pintype "passive"))
      (node (ref "R42") (pin "1") (pinfunction "1_1") (pintype "passive"))
    )
    (net (code "26") (name "Net-(DW1N-PadA)") (class "Default")
      (node (ref "DW1N") (pin "A") (pinfunction "A_A") (pintype "passive"))
      (node (ref "R1") (pin "1") (pinfunction "1_1") (pintype "passive"))
    )
    (net (code "27") (name "Net-(DW1R-PadA)") (class "Default")
      (node (ref "DW1R") (pin "A") (pinfunction "A_A") (pintype "passive"))
      (node (ref "R2") (pin "1") (pinfunction "1_1") (pintype "passive"))
    )
    (net (code "28") (name "Net-(DW2AN-PadA)") (class "Default")
      (node (ref "DW2AN") (pin "A") (pinfunction "A_A") (pintype "passive"))
      (node (ref "R4") (pin "1") (pinfunction "1_1") (pintype "passive"))
    )
    (net (code "29") (name "Net-(DW2AR-PadA)") (class "Default")
      (node (ref "DW2AR") (pin "A") (pinfunction "A_A") (pintype "passive"))
      (node (ref "R5") (pin "1") (pinfunction "1_1") (pintype "passive"))
    )
    (net (code "30") (name "Net-(DW2BN-PadA)") (class "Default")
      (node (ref "DW2BN") (pin "A") (pinfunction "A_A") (pintype "passive"))
      (node (ref "R7") (pin "1") (pinfunction "1_1") (pintype "passive"))
    )
    (net (code "31") (name "Net-(DW2BR-PadA)") (class "Default")
      (node (ref "DW2BR") (pin "A") (pinfunction "A_A") (pintype "passive"))
      (node (ref "R8") (pin "1") (pinfunction "1_1") (pintype "passive"))
    )
    (net (code "32") (name "Net-(DW7AN-PadA)") (class "Default")
      (node (ref "DW7AN") (pin "A") (pinfunction "A_A") (pintype "passive"))
      (node (ref "R18") (pin "1") (pinfunction "1_1") (pintype "passive"))
    )
    (net (code "33") (name "Net-(DW7AR-PadA)") (class "Default")
      (node (ref "DW7AR") (pin "A") (pinfunction "A_A") (pintype "passive"))
      (node (ref "R19") (pin "1") (pinfunction "1_1") (pintype "passive"))
    )
    (net (code "34") (name "Net-(DW7BN-PadA)") (class "Default")
      (node (ref "DW7BN") (pin "A") (pinfunction "A_A") (pintype "passive"))
      (node (ref "R21") (pin "1") (pinfunction "1_1") (pintype "passive"))
    )
    (net (code "35") (name "Net-(DW7BR-PadA)") (class "Default")
      (node (ref "DW7BR") (pin "A") (pinfunction "A_A") (pintype "passive"))
      (node (ref "R22") (pin "1") (pinfunction "1_1") (pintype "passive"))
    )
    (net (code "36") (name "Net-(DW34N-PadA)") (class "Default")
      (node (ref "DW34N") (pin "A") (pinfunction "A_A") (pintype "passive"))
      (node (ref "R10") (pin "1") (pinfunction "1_1") (pintype "passive"))
    )
    (net (code "37") (name "Net-(DW34N1-PadA)") (class "Default")
      (node (ref "DW34N1") (pin "A") (pinfunction "A_A") (pintype "passive"))
      (node (ref "R13") (pin "1") (pinfunction "1_1") (pintype "passive"))
    )
    (net (code "38") (name "Net-(DW34R-PadA)") (class "Default")
      (node (ref "DW34R") (pin "A") (pinfunction "A_A") (pintype "passive"))
      (node (ref "R11") (pin "1") (pinfunction "1_1") (pintype "passive"))
    )
    (net (code "39") (name "Net-(DW56N-PadA)") (class "Default")
      (node (ref "DW56N") (pin "A") (pinfunction "A_A") (pintype "passive"))
      (node (ref "R14") (pin "1") (pinfunction "1_1") (pintype "passive"))
    )
    (net (code "40") (name "Net-(DW56N1-PadA)") (class "Default")
      (node (ref "DW56N1") (pin "A") (pinfunction "A_A") (pintype "passive"))
      (node (ref "R17") (pin "1") (pinfunction "1_1") (pintype "passive"))
    )
    (net (code "41") (name "Net-(DW56R-PadA)") (class "Default")
      (node (ref "DW56R") (pin "A") (pinfunction "A_A") (pintype "passive"))
      (node (ref "R15") (pin "1") (pinfunction "1_1") (pintype "passive"))
    )
    (net (code "42") (name "Net-(DW89N-PadA)") (class "Default")
      (node (ref "DW89N") (pin "A") (pinfunction "A_A") (pintype "passive"))
      (node (ref "R24") (pin "1") (pinfunction "1_1") (pintype "passive"))
    )
    (net (code "43") (name "Net-(DW89N1-PadA)") (class "Default")
      (node (ref "DW89N1") (pin "A") (pinfunction "A_A") (pintype "passive"))
      (node (ref "R27") (pin "1") (pinfunction "1_1") (pintype "passive"))
    )
    (net (code "44") (name "Net-(DW89R-PadA)") (class "Default")
      (node (ref "DW89R") (pin "A") (pinfunction "A_A") (pintype "passive"))
      (node (ref "R25") (pin "1") (pinfunction "1_1") (pintype "passive"))
    )
    (net (code "45") (name "Net-(DW1011N-PadA)") (class "Default")
      (node (ref "DW1011N") (pin "A") (pinfunction "A_A") (pintype "passive"))
      (node (ref "R28") (pin "1") (pinfunction "1_1") (pintype "passive"))
    )
    (net (code "46") (name "Net-(DW1011N1-PadA)") (class "Default")
      (node (ref "DW1011N1") (pin "A") (pinfunction "A_A") (pintype "passive"))
      (node (ref "R31") (pin "1") (pinfunction "1_1") (pintype "passive"))
    )
    (net (code "47") (name "Net-(DW1011R-PadA)") (class "Default")
      (node (ref "DW1011R") (pin "A") (pinfunction "A_A") (pintype "passive"))
      (node (ref "R29") (pin "1") (pinfunction "1_1") (pintype "passive"))
    )
    (net (code "48") (name "Net-(LOCK-1.1)") (class "Default")
      (node (ref "LOCK") (pin "1") (pinfunction "1.1_1") (pintype "passive"))
      (node (ref "R45") (pin "2") (pinfunction "2_2") (pintype "passive"))
    )
    (net (code "49") (name "Net-(Q1-D)") (class "Default")
      (node (ref "DW1N") (pin "C") (pinfunction "C_C") (pintype "passive"))
      (node (ref "Q1") (pin "3") (pinfunction "D_3") (pintype "passive"))
    )
    (net (code "50") (name "Net-(Q2-D)") (class "Default")
      (node (ref "DW2AN") (pin "C") (pinfunction "C_C") (pintype "passive"))
      (node (ref "Q2") (pin "3") (pinfunction "D_3") (pintype "passive"))
    )
    (net (code "51") (name "Net-(Q3-D)") (class "Default")
      (node (ref "Q3") (pin "3") (pinfunction "D_3") (pintype "passive"))
      (node (ref "R2") (pin "2") (pinfunction "2_2") (pintype "passive"))
    )
    (net (code "52") (name "Net-(Q4-D)") (class "Default")
      (node (ref "Q4") (pin "3") (pinfunction "D_3") (pintype "passive"))
      (node (ref "R5") (pin "2") (pinfunction "2_2") (pintype "passive"))
    )
    (net (code "53") (name "Net-(Q5-D)") (class "Default")
      (node (ref "DW2BN") (pin "C") (pinfunction "C_C") (pintype "passive"))
      (node (ref "Q5") (pin "3") (pinfunction "D_3") (pintype "passive"))
    )
    (net (code "54") (name "Net-(Q6-D)") (class "Default")
      (node (ref "Q6") (pin "3") (pinfunction "D_3") (pintype "passive"))
      (node (ref "R8") (pin "2") (pinfunction "2_2") (pintype "passive"))
    )
    (net (code "55") (name "Net-(Q7-D)") (class "Default")
      (node (ref "DW34N") (pin "C") (pinfunction "C_C") (pintype "passive"))
      (node (ref "DW34N1") (pin "C") (pinfunction "C_C") (pintype "passive"))
      (node (ref "Q7") (pin "3") (pinfunction "D_3") (pintype "passive"))
    )
    (net (code "56") (name "Net-(Q8-D)") (class "Default")
      (node (ref "Q8") (pin "3") (pinfunction "D_3") (pintype "passive"))
      (node (ref "R11") (pin "2") (pinfunction "2_2") (pintype "passive"))
    )
    (net (code "57") (name "Net-(Q9-D)") (class "Default")
      (node (ref "DW56N") (pin "C") (pinfunction "C_C") (pintype "passive"))
      (node (ref "DW56N1") (pin "C") (pinfunction "C_C") (pintype "passive"))
      (node (ref "Q9") (pin "3") (pinfunction "D_3") (pintype "passive"))
    )
    (net (code "58") (name "Net-(Q10-D)") (class "Default")
      (node (ref "Q10") (pin "3") (pinfunction "D_3") (pintype "passive"))
      (node (ref "R15") (pin "2") (pinfunction "2_2") (pintype "passive"))
    )
    (net (code "59") (name "Net-(Q11-D)") (class "Default")
      (node (ref "DW7AN") (pin "C") (pinfunction "C_C") (pintype "passive"))
      (node (ref "Q11") (pin "3") (pinfunction "D_3") (pintype "passive"))
    )
    (net (code "60") (name "Net-(Q12-D)") (class "Default")
      (node (ref "Q12") (pin "3") (pinfunction "D_3") (pintype "passive"))
      (node (ref "R19") (pin "2") (pinfunction "2_2") (pintype "passive"))
    )
    (net (code "61") (name "Net-(Q13-D)") (class "Default")
      (node (ref "DW7BN") (pin "C") (pinfunction "C_C") (pintype "passive"))
      (node (ref "Q13") (pin "3") (pinfunction "D_3") (pintype "passive"))
    )
    (net (code "62") (name "Net-(Q14-D)") (class "Default")
      (node (ref "Q14") (pin "3") (pinfunction "D_3") (pintype "passive"))
      (node (ref "R22") (pin "2") (pinfunction "2_2") (pintype "passive"))
    )
    (net (code "63") (name "Net-(Q15-D)") (class "Default")
      (node (ref "DW89N") (pin "C") (pinfunction "C_C") (pintype "passive"))
      (node (ref "DW89N1") (pin "C") (pinfunction "C_C") (pintype "passive"))
      (node (ref "Q15") (pin "3") (pinfunction "D_3") (pintype "passive"))
    )
    (net (code "64") (name "Net-(Q16-D)") (class "Default")
      (node (ref "Q16") (pin "3") (pinfunction "D_3") (pintype "passive"))
      (node (ref "R25") (pin "2") (pinfunction "2_2") (pintype "passive"))
    )
    (net (code "65") (name "Net-(Q17-D)") (class "Default")
      (node (ref "DW1011N") (pin "C") (pinfunction "C_C") (pintype "passive"))
      (node (ref "DW1011N1") (pin "C") (pinfunction "C_C") (pintype "passive"))
      (node (ref "Q17") (pin "3") (pinfunction "D_3") (pintype "passive"))
    )
    (net (code "66") (name "Net-(Q18-D)") (class "Default")
      (node (ref "Q18") (pin "3") (pinfunction "D_3") (pintype "passive"))
      (node (ref "R29") (pin "2") (pinfunction "2_2") (pintype "passive"))
    )
    (net (code "67") (name "Net-(Q19-D)") (class "Default")
      (node (ref "DTRK1") (pin "C") (pinfunction "C_C") (pintype "passive"))
      (node (ref "Q19") (pin "3") (pinfunction "D_3") (pintype "passive"))
    )
    (net (code "68") (name "Net-(Q20-D)") (class "Default")
      (node (ref "DTRK2") (pin "C") (pinfunction "C_C") (pintype "passive"))
      (node (ref "Q20") (pin "3") (pinfunction "D_3") (pintype "passive"))
    )
    (net (code "69") (name "Net-(Q21-D)") (class "Default")
      (node (ref "DTRK3") (pin "C") (pinfunction "C_C") (pintype "passive"))
      (node (ref "Q21") (pin "3") (pinfunction "D_3") (pintype "passive"))
    )
    (net (code "70") (name "Net-(Q22-D)") (class "Default")
      (node (ref "DTRK4") (pin "C") (pinfunction "C_C") (pintype "passive"))
      (node (ref "Q22") (pin "3") (pinfunction "D_3") (pintype "passive"))
    )
    (net (code "71") (name "Net-(Q23-D)") (class "Default")
      (node (ref "DTRK5") (pin "C") (pinfunction "C_C") (pintype "passive"))
      (node (ref "Q23") (pin "3") (pinfunction "D_3") (pintype "passive"))
    )
    (net (code "72") (name "Net-(Q24-D)") (class "Default")
      (node (ref "DTRK6") (pin "C") (pinfunction "C_C") (pintype "passive"))
      (node (ref "Q24") (pin "3") (pinfunction "D_3") (pintype "passive"))
    )
    (net (code "73") (name "Net-(Q25-D)") (class "Default")
      (node (ref "DLOCK") (pin "C") (pinfunction "C_C") (pintype "passive"))
      (node (ref "Q25") (pin "3") (pinfunction "D_3") (pintype "passive"))
    )
    (net (code "74") (name "Net-(TRK1-1.1)") (class "Default")
      (node (ref "R34") (pin "2") (pinfunction "2_2") (pintype "passive"))
      (node (ref "TRK1") (pin "1") (pinfunction "1.1_1") (pintype "passive"))
    )
    (net (code "75") (name "Net-(TRK2-1.1)") (class "Default")
      (node (ref "R35") (pin "2") (pinfunction "2_2") (pintype "passive"))
      (node (ref "TRK2") (pin "1") (pinfunction "1.1_1") (pintype "passive"))
    )
    (net (code "76") (name "Net-(TRK3-1.1)") (class "Default")
      (node (ref "R37") (pin "2") (pinfunction "2_2") (pintype "passive"))
      (node (ref "TRK3") (pin "1") (pinfunction "1.1_1") (pintype "passive"))
    )
    (net (code "77") (name "Net-(TRK4-1.1)") (class "Default")
      (node (ref "R39") (pin "2") (pinfunction "2_2") (pintype "passive"))
      (node (ref "TRK4") (pin "1") (pinfunction "1.1_1") (pintype "passive"))
    )
    (net (code "78") (name "Net-(TRK5-1.1)") (class "Default")
      (node (ref "R41") (pin "2") (pinfunction "2_2") (pintype "passive"))
      (node (ref "TRK5") (pin "1") (pinfunction "1.1_1") (pintype "passive"))
    )
    (net (code "79") (name "Net-(TRK6-1.1)") (class "Default")
      (node (ref "R43") (pin "2") (pinfunction "2_2") (pintype "passive"))
      (node (ref "TRK6") (pin "1") (pinfunction "1.1_1") (pintype "passive"))
    )
    (net (code "80") (name "Net-(W1-1.1)") (class "Default")
      (node (ref "R3") (pin "2") (pinfunction "2_2") (pintype "passive"))
      (node (ref "W1") (pin "1") (pinfunction "1.1_1") (pintype "passive"))
    )
    (net (code "81") (name "Net-(W2A-1.1)") (class "Default")
      (node (ref "R6") (pin "2") (pinfunction "2_2") (pintype "passive"))
      (node (ref "W2A") (pin "1") (pinfunction "1.1_1") (pintype "passive"))
    )
    (net (code "82") (name "Net-(W2B-1.1)") (class "Default")
      (node (ref "R9") (pin "2") (pinfunction "2_2") (pintype "passive"))
      (node (ref "W2B") (pin "1") (pinfunction "1.1_1") (pintype "passive"))
    )
    (net (code "83") (name "Net-(W7A-1.1)") (class "Default")
      (node (ref "R20") (pin "2") (pinfunction "2_2") (pintype "passive"))
      (node (ref "W7A") (pin "1") (pinfunction "1.1_1") (pintype "passive"))
    )
    (net (code "84") (name "Net-(W7B-1.1)") (class "Default")
      (node (ref "R23") (pin "2") (pinfunction "2_2") (pintype "passive"))
      (node (ref "W7B") (pin "1") (pinfunction "1.1_1") (pintype "passive"))
    )
    (net (code "85") (name "Net-(W34-1.1)") (class "Default")
      (node (ref "R12") (pin "2") (pinfunction "2_2") (pintype "passive"))
      (node (ref "W34") (pin "1") (pinfunction "1.1_1") (pintype "passive"))
    )
    (net (code "86") (name "Net-(W56-1.1)") (class "Default")
      (node (ref "R16") (pin "2") (pinfunction "2_2") (pintype "passive"))
      (node (ref "W56") (pin "1") (pinfunction "1.1_1") (pintype "passive"))
    )
    (net (code "87") (name "Net-(W89-1.1)") (class "Default")
      (node (ref "R26") (pin "2") (pinfunction "2_2") (pintype "passive"))
      (node (ref "W89") (pin "1") (pinfunction "1.1_1") (pintype "passive"))
    )
    (net (code "88") (name "Net-(W1011-1.1)") (class "Default")
      (node (ref "R30") (pin "2") (pinfunction "2_2") (pintype "passive"))
      (node (ref "W1011") (pin "1") (pinfunction "1.1_1") (pintype "passive"))
    )
    (net (code "89") (name "unconnected-(LOCK-1.2-Pad2)") (class "Default")
      (node (ref "LOCK") (pin "2") (pinfunction "1.2_2") (pintype "passive"))
    )
    (net (code "90") (name "unconnected-(TRK1-1.2-Pad2)") (class "Default")
      (node (ref "TRK1") (pin "2") (pinfunction "1.2_2") (pintype "passive"))
    )
    (net (code "91") (name "unconnected-(TRK2-1.2-Pad2)") (class "Default")
      (node (ref "TRK2") (pin "2") (pinfunction "1.2_2") (pintype "passive"))
    )
    (net (code "92") (name "unconnected-(TRK3-1.2-Pad2)") (class "Default")
      (node (ref "TRK3") (pin "2") (pinfunction "1.2_2") (pintype "passive"))
    )
    (net (code "93") (name "unconnected-(TRK4-1.2-Pad2)") (class "Default")
      (node (ref "TRK4") (pin "2") (pinfunction "1.2_2") (pintype "passive"))
    )
    (net (code "94") (name "unconnected-(TRK5-1.2-Pad2)") (class "Default")
      (node (ref "TRK5") (pin "2") (pinfunction "1.2_2") (pintype "passive"))
    )
    (net (code "95") (name "unconnected-(TRK6-1.2-Pad2)") (class "Default")
      (node (ref "TRK6") (pin "2") (pinfunction "1.2_2") (pintype "passive"))
    )
    (net (code "96") (name "unconnected-(W1-1.2-Pad2)") (class "Default")
      (node (ref "W1") (pin "2") (pinfunction "1.2_2") (pintype "passive"))
    )
    (net (code "97") (name "unconnected-(W2A-1.2-Pad2)") (class "Default")
      (node (ref "W2A") (pin "2") (pinfunction "1.2_2") (pintype "passive"))
    )
    (net (code "98") (name "unconnected-(W2B-1.2-Pad2)") (class "Default")
      (node (ref "W2B") (pin "2") (pinfunction "1.2_2") (pintype "passive"))
    )
    (net (code "99") (name "unconnected-(W7A-1.2-Pad2)") (class "Default")
      (node (ref "W7A") (pin "2") (pinfunction "1.2_2") (pintype "passive"))
    )
    (net (code "100") (name "unconnected-(W7B-1.2-Pad2)") (class "Default")
      (node (ref "W7B") (pin "2") (pinfunction "1.2_2") (pintype "passive"))
    )
    (net (code "101") (name "unconnected-(W34-1.2-Pad2)") (class "Default")
      (node (ref "W34") (pin "2") (pinfunction "1.2_2") (pintype "passive"))
    )
    (net (code "102") (name "unconnected-(W56-1.2-Pad2)") (class "Default")
      (node (ref "W56") (pin "2") (pinfunction "1.2_2") (pintype "passive"))
    )
    (net (code "103") (name "unconnected-(W89-1.2-Pad2)") (class "Default")
      (node (ref "W89") (pin "2") (pinfunction "1.2_2") (pintype "passive"))
    )
    (net (code "104") (name "unconnected-(W1011-1.2-Pad2)") (class "Default")
      (node (ref "W1011") (pin "2") (pinfunction "1.2_2") (pintype "passive"))
    )
  )
)
